# Regulator.net
KiCad netlist of a schematic drawn in Altium Designer
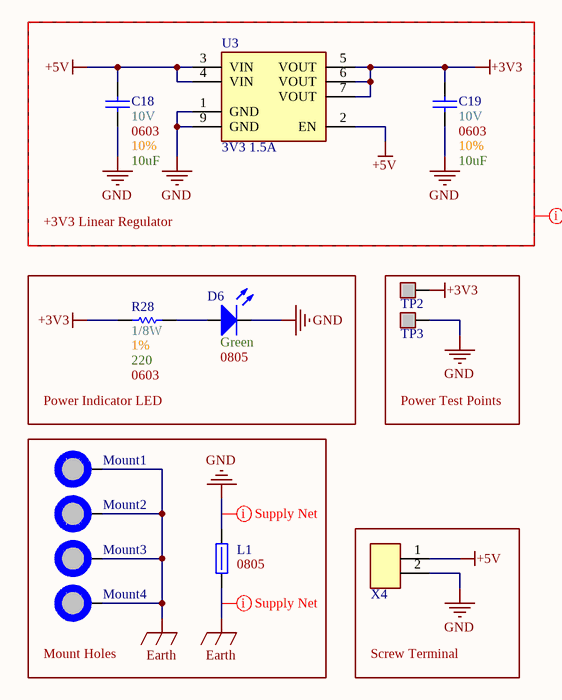
[diagram p0: Regulator.SchDoc]

(export (version "E")
  (design (tool "Eeschema 10.0.6"))
  (components
    (comp (ref "C18")
      (value "[Cap] 0603 10uF 10% 10V")
      (footprint "[Cap] SMD 0603")
      (description "CL10A106KP8NNNC")
      (fields
        (field (name "MAX VOLTAGE") "10V")
        (field (name "SIZE PACKAGE") "0603")
        (field (name "TOLERANCE") "10%")
        (field (name "CAPACITANCE") "10uF")
      )
      (libsource (lib "Capacitors") (part "[Cap] 0603 10uF 10% 10V"))
    )
    (comp (ref "C19")
      (value "[Cap] 0603 10uF 10% 10V")
      (footprint "[Cap] SMD 0603")
      (description "CL10A106KP8NNNC")
      (fields
        (field (name "MAX VOLTAGE") "10V")
        (field (name "SIZE PACKAGE") "0603")
        (field (name "TOLERANCE") "10%")
        (field (name "CAPACITANCE") "10uF")
      )
      (libsource (lib "Capacitors") (part "[Cap] 0603 10uF 10% 10V"))
    )
    (comp (ref "D6")
      (value "[LED] SMD 0805 Green")
      (footprint "[LED] SMD 0805")
      (description "LG R971-KN-1-0-20-R18")
      (fields (field (name "COLOR") "Green") (field (name "SIZE PACKAGE") "0805"))
      (libsource (lib "LEDs") (part "[LED] SMD 0805 Green"))
    )
    (comp (ref "L1")
      (value "652-MH2029-300Y")
      (footprint "[Ferrite] SMD 0805")
      (fields (field (name "SIZE PACKAGE") "0805"))
      (libsource (lib "Ferrite Beads") (part "[Ferrite] SMD 0805 3A 30ohm"))
    )
    (comp (ref "Mount1")
      (value "M3 Mount Hole")
      (footprint "[Mount] M3 Mount Hole")
      (description "Place at least 4.5mm from board edge. Plated.")
      (libsource (lib "RADM Connectors") (part "[Mount] M3 Mount Hole"))
    )
    (comp (ref "Mount2")
      (value "M3 Mount Hole")
      (footprint "[Mount] M3 Mount Hole")
      (description "Place at least 4.5mm from board edge. Plated.")
      (libsource (lib "RADM Connectors") (part "[Mount] M3 Mount Hole"))
    )
    (comp (ref "Mount3")
      (value "M3 Mount Hole")
      (footprint "[Mount] M3 Mount Hole")
      (description "Place at least 4.5mm from board edge. Plated.")
      (libsource (lib "RADM Connectors") (part "[Mount] M3 Mount Hole"))
    )
    (comp (ref "Mount4")
      (value "M3 Mount Hole")
      (footprint "[Mount] M3 Mount Hole")
      (description "Place at least 4.5mm from board edge. Plated.")
      (libsource (lib "RADM Connectors") (part "[Mount] M3 Mount Hole"))
    )
    (comp (ref "R28")
      (value "[220] SMD 0603 1% 1/10W")
      (footprint "[Res] SMD 0603")
      (description "CRGCQ0805F220R")
      (fields
        (field (name "WATTAGE") "1/8W")
        (field (name "TOLERANCE") "1%")
        (field (name "RESISTANCE") "220")
        (field (name "SIZE PACKAGE") "0603")
      )
      (libsource (lib "Resistors") (part "[220] SMD 0603 1% 1/10W"))
    )
    (comp (ref "TP2")
      (value "[THM] Thru-Hole")
      (footprint "[THM] White")
      (description "5012")
      (libsource (lib "Test Points") (part "[THM] Thru-Hole"))
    )
    (comp (ref "TP3")
      (value "[THM] Thru-Hole")
      (footprint "[THM] White")
      (description "5012")
      (libsource (lib "Test Points") (part "[THM] Thru-Hole"))
    )
    (comp (ref "U3")
      (value "3V3 1.5A")
      (footprint "[Linear] 3V3 1.5A")
      (description "AP7362A-33SP-13")
      (libsource (lib "Voltage Regulators") (part "[Linear] 3V3 1.5A"))
    )
    (comp (ref "X4")
      (value "2pin Screw Terminal")
      (footprint "[Screw Terminal] 2pin 5mm")
      (description "TB002-500-02BE")
      (libsource (lib "Connectors") (part "[Screw Terminal] 2pin"))
    )
  )
  (nets
    (net (code "1") (name "+3V3") (class "Default")
      (node (ref "C19") (pin "2") (pinfunction "2_2") (pintype "passive"))
      (node (ref "R28") (pin "1") (pinfunction "1_1") (pintype "passive"))
      (node (ref "TP2") (pin "1") (pinfunction "1_1") (pintype "passive"))
      (node (ref "U3") (pin "5") (pinfunction "VOUT_5") (pintype "passive"))
      (node (ref "U3") (pin "6") (pinfunction "VOUT_6") (pintype "passive"))
      (node (ref "U3") (pin "7") (pinfunction "VOUT_7") (pintype "passive"))
    )
    (net (code "2") (name "+5V") (class "Default")
      (node (ref "C18") (pin "2") (pinfunction "2_2") (pintype "passive"))
      (node (ref "U3") (pin "2") (pinfunction "EN_2") (pintype "passive"))
      (node (ref "U3") (pin "3") (pinfunction "VIN_3") (pintype "passive"))
      (node (ref "U3") (pin "4") (pinfunction "VIN_4") (pintype "passive"))
      (node (ref "X4") (pin "1") (pintype "power_in"))
    )
    (net (code "3") (name "Earth") (class "Default")
      (node (ref "L1") (pin "1") (pinfunction "1_1") (pintype "passive"))
      (node (ref "Mount1") (pin "1") (pintype "power_in"))
      (node (ref "Mount2") (pin "1") (pintype "power_in"))
      (node (ref "Mount3") (pin "1") (pintype "power_in"))
      (node (ref "Mount4") (pin "1") (pintype "power_in"))
    )
    (net (code "4") (name "GND") (class "Default")
      (node (ref "C18") (pin "1") (pinfunction "1_1") (pintype "passive"))
      (node (ref "C19") (pin "1") (pinfunction "1_1") (pintype "passive"))
      (node (ref "D6") (pin "2") (pinfunction "Cathode_2") (pintype "passive"))
      (node (ref "L1") (pin "2") (pinfunction "2_2") (pintype "passive"))
      (node (ref "TP3") (pin "1") (pinfunction "1_1") (pintype "passive"))
      (node (ref "U3") (pin "1") (pinfunction "GND_1") (pintype "passive"))
      (node (ref "U3") (pin "9") (pinfunction "GND_9") (pintype "passive"))
      (node (ref "X4") (pin "2") (pintype "power_in"))
    )
    (net (code "5") (name "Net-(D6-Anode)") (class "Default")
      (node (ref "D6") (pin "1") (pinfunction "Anode_1") (pintype "passive"))
      (node (ref "R28") (pin "2") (pinfunction "2_2") (pintype "passive"))
    )
  )
)
